# 02_ZIGBEE_CC2530.net
KiCad netlist of a schematic drawn in Altium Designer
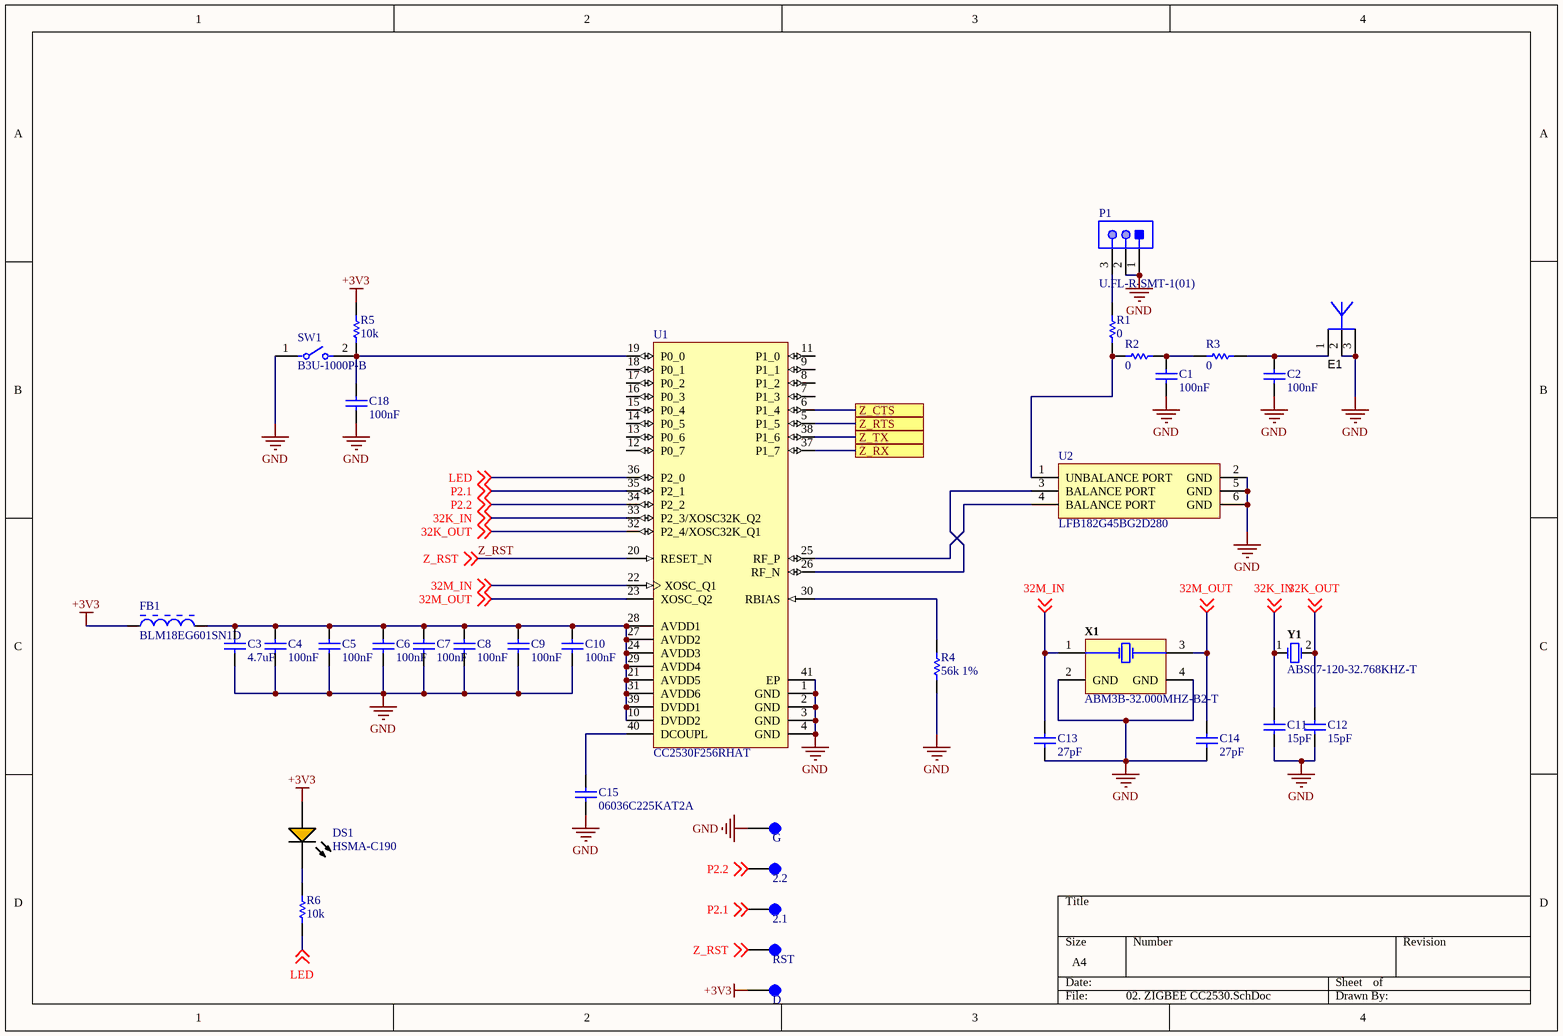
[diagram p0: 02. ZIGBEE CC2530.SchDoc]

(export (version "E")
  (design (tool "Eeschema 10.0.6"))
  (components
    (comp (ref "2.1") (value "Test Point") (footprint "TP") (libsource (lib "SyTungNguyen") (part "TP")))
    (comp (ref "2.2") (value "Test Point") (footprint "TP") (libsource (lib "SyTungNguyen") (part "TP")))
    (comp (ref "C1")
      (value "100nF")
      (footprint "CAPC1005X56X25NL10T15")
      (fields
        (field (name "MANUFACTURER") "AVX Interconnect / Elco")
        (field (name "PART NUMBER") "04026D104KAT2A")
      )
      (libsource (lib "Altium Content Vault") (part "CAP"))
    )
    (comp (ref "C2")
      (value "100nF")
      (footprint "CAPC1005X56X25NL10T15")
      (fields
        (field (name "MANUFACTURER") "AVX Interconnect / Elco")
        (field (name "PART NUMBER") "04026D104KAT2A")
      )
      (libsource (lib "Altium Content Vault") (part "CAP"))
    )
    (comp (ref "C3")
      (value "4.7uF")
      (footprint "CAPC1608X90X35NL10T15")
      (fields (field (name "PART NUMBER") "GRM188R6YA475KE15D") (field (name "MANUFACTURER") "Murata"))
      (libsource (lib "Altium Content Vault") (part "CAP"))
    )
    (comp (ref "C4")
      (value "100nF")
      (footprint "CAPC1005X56X25NL10T15")
      (fields
        (field (name "MANUFACTURER") "AVX Interconnect / Elco")
        (field (name "PART NUMBER") "04026D104KAT2A")
      )
      (libsource (lib "Altium Content Vault") (part "CAP"))
    )
    (comp (ref "C5")
      (value "100nF")
      (footprint "CAPC1005X56X25NL10T15")
      (fields
        (field (name "MANUFACTURER") "AVX Interconnect / Elco")
        (field (name "PART NUMBER") "04026D104KAT2A")
      )
      (libsource (lib "Altium Content Vault") (part "CAP"))
    )
    (comp (ref "C6")
      (value "100nF")
      (footprint "CAPC1005X56X25NL10T15")
      (fields
        (field (name "MANUFACTURER") "AVX Interconnect / Elco")
        (field (name "PART NUMBER") "04026D104KAT2A")
      )
      (libsource (lib "Altium Content Vault") (part "CAP"))
    )
    (comp (ref "C7")
      (value "100nF")
      (footprint "CAPC1005X56X25NL10T15")
      (fields
        (field (name "MANUFACTURER") "AVX Interconnect / Elco")
        (field (name "PART NUMBER") "04026D104KAT2A")
      )
      (libsource (lib "Altium Content Vault") (part "CAP"))
    )
    (comp (ref "C8")
      (value "100nF")
      (footprint "CAPC1005X56X25NL10T15")
      (fields
        (field (name "MANUFACTURER") "AVX Interconnect / Elco")
        (field (name "PART NUMBER") "04026D104KAT2A")
      )
      (libsource (lib "Altium Content Vault") (part "CAP"))
    )
    (comp (ref "C9")
      (value "100nF")
      (footprint "CAPC1005X56X25NL10T15")
      (fields
        (field (name "MANUFACTURER") "AVX Interconnect / Elco")
        (field (name "PART NUMBER") "04026D104KAT2A")
      )
      (libsource (lib "Altium Content Vault") (part "CAP"))
    )
    (comp (ref "C10")
      (value "100nF")
      (footprint "CAPC1005X56X25NL10T15")
      (fields
        (field (name "MANUFACTURER") "AVX Interconnect / Elco")
        (field (name "PART NUMBER") "04026D104KAT2A")
      )
      (libsource (lib "Altium Content Vault") (part "CAP"))
    )
    (comp (ref "C11")
      (value "15pF")
      (footprint "CAPC1005X56X25NL10T15")
      (fields
        (field (name "PART NUMBER") "04025A270FAT2A")
        (field (name "MANUFACTURER") "AVX Interconnect / Elco")
      )
      (libsource (lib "Altium Content Vault") (part "CAP"))
    )
    (comp (ref "C12")
      (value "15pF")
      (footprint "CAPC1005X56X25NL10T15")
      (fields
        (field (name "PART NUMBER") "04025A270FAT2A")
        (field (name "MANUFACTURER") "AVX Interconnect / Elco")
      )
      (libsource (lib "Altium Content Vault") (part "CAP"))
    )
    (comp (ref "C13")
      (value "27pF")
      (footprint "CAPC1005X56X25NL10T15")
      (fields
        (field (name "PART NUMBER") "04025A270FAT2A")
        (field (name "MANUFACTURER") "AVX Interconnect / Elco")
      )
      (libsource (lib "Altium Content Vault") (part "CAP"))
    )
    (comp (ref "C14")
      (value "27pF")
      (footprint "CAPC1005X56X25NL10T15")
      (fields
        (field (name "PART NUMBER") "04025A270FAT2A")
        (field (name "MANUFACTURER") "AVX Interconnect / Elco")
      )
      (libsource (lib "Altium Content Vault") (part "CAP"))
    )
    (comp (ref "C15")
      (value "06036C225KAT2A")
      (footprint "CAPC1608X90X35NL15T15")
      (fields (field (name "MANUFACTURER") "AVX Interconnect / Elco"))
      (libsource (lib "Altium Content Vault") (part "CAP"))
    )
    (comp (ref "C18")
      (value "100nF")
      (footprint "CAPC1005X56X25NL10T15")
      (fields
        (field (name "MANUFACTURER") "AVX Interconnect / Elco")
        (field (name "PART NUMBER") "04026D104KAT2A")
      )
      (libsource (lib "Altium Content Vault") (part "CAP"))
    )
    (comp (ref "D") (value "Test Point") (footprint "TP") (libsource (lib "SyTungNguyen") (part "TP")))
    (comp (ref "DS1")
      (value "HSMA-C190")
      (footprint "AVAG-HSMX-C190_V")
      (description "LED Uni-Color Amber, 60 mW, 20 mA, -40 to 85 degC, 2-Pin SMD, RoHS, Tape and Reel")
      (fields (field (name "TOLERANCE") "20ppm"))
      (libsource (lib "Altium Content Vault") (part "LED-AMBER-AK-2"))
    )
    (comp (ref "E1")
      (value "ANTENNA_DN007A")
      (footprint "2.4Ghz TI ANTENNA_DN007A")
      (description "2.4GHz PCB Antenna.  There is nothing to buy or mount.")
      (fields (field (name "SYMBOLCREATOR") "a0412235") (field (name "PUBLISHER") "Texas Instruments"))
      (libsource (lib "SyTungNguyen") (part "ANTENNA_DN007A"))
    )
    (comp (ref "FB1")
      (value "BLM18EG601SN1D")
      (footprint "MURA-BLM18-F-H1-CHIP-2_V")
      (fields (field (name "MANUFACTURER") "Murata"))
      (libsource (lib "Altium Content Vault") (part "MURA-FB-2"))
    )
    (comp (ref "G") (value "Test Point") (footprint "TP") (libsource (lib "SyTungNguyen") (part "TP")))
    (comp (ref "P1")
      (value "U.FL-R-SMT-1(01)")
      (footprint "HRS-U.FL-R-SMT-3_V")
      (description "Ultra Small Coaxial Connector, 6 GHz, -40 to 90 degC, 3-Pin SMD, RoHS, Bulk")
      (fields (field (name "MANUFACTURER") "Hirose Electric"))
      (libsource (lib "Altium Content Vault") (part "CN-1P-M-R3"))
    )
    (comp (ref "R1")
      (value "0")
      (footprint "RESC1005X40X25NL05T05")
      (description "Chip Resistor, 10 KOhm, +/- 1%, 0.1 W, -55 to 155 degC, 0402 (1005 Metric), RoHS, Tape and Reel")
      (fields (field (name "TOLERANCE") "1%") (field (name "MANUFACTURER") "Panasonic"))
      (libsource (lib "Altium Content Vault") (part "RES-2"))
    )
    (comp (ref "R2")
      (value "0")
      (footprint "RESC1005X40X25NL05T05")
      (description "Chip Resistor, 10 KOhm, +/- 1%, 0.1 W, -55 to 155 degC, 0402 (1005 Metric), RoHS, Tape and Reel")
      (fields (field (name "TOLERANCE") "1%") (field (name "MANUFACTURER") "Panasonic"))
      (libsource (lib "Altium Content Vault") (part "RES-2"))
    )
    (comp (ref "R3")
      (value "0")
      (footprint "RESC1005X40X25NL05T05")
      (description "Chip Resistor, 10 KOhm, +/- 1%, 0.1 W, -55 to 155 degC, 0402 (1005 Metric), RoHS, Tape and Reel")
      (fields (field (name "TOLERANCE") "1%") (field (name "MANUFACTURER") "Panasonic"))
      (libsource (lib "Altium Content Vault") (part "RES-2"))
    )
    (comp (ref "R4")
      (value "56k 1%")
      (footprint "RESC1609X50X30NL10T20")
      (fields (field (name "PART NUMBER") "CRCW060356K0FKEA") (field (name "MANUFACTURER") "Vishay Dale"))
      (libsource (lib "Altium Content Vault") (part "RES"))
    )
    (comp (ref "R5")
      (value "10k")
      (footprint "RESC1005X40X25NL05T05")
      (description "Chip Resistor, 10 KOhm, +/- 1%, 0.1 W, -55 to 155 degC, 0402 (1005 Metric), RoHS, Tape and Reel")
      (fields (field (name "TOLERANCE") "1%") (field (name "MANUFACTURER") "Panasonic"))
      (libsource (lib "Altium Content Vault") (part "RES-2"))
    )
    (comp (ref "R6")
      (value "10k")
      (footprint "RESC1005X40X25NL05T05")
      (description "Chip Resistor, 10 KOhm, +/- 1%, 0.1 W, -55 to 155 degC, 0402 (1005 Metric), RoHS, Tape and Reel")
      (fields (field (name "TOLERANCE") "1%") (field (name "MANUFACTURER") "Panasonic"))
      (libsource (lib "Altium Content Vault") (part "RES-2"))
    )
    (comp (ref "RST") (value "Test Point") (footprint "TP") (libsource (lib "SyTungNguyen") (part "TP")))
    (comp (ref "SW1")
      (value "B3U-1000P-B")
      (footprint "FP-B3U-1000P-B-MFG")
      (description "SWITCH TACTILE SPST-NO 0.05A 12V")
      (fields
        (field (name "OCTOPART") "https://octopart.com/b3u-1000p-b-omron-1057356")
        (field (name "MANUFACTURER") "Omron")
      )
      (libsource (lib "Altium Content Vault") (part "bb27bde45df87f1f469753f287ef5ae"))
    )
    (comp (ref "U1")
      (value "CC2530F256RHAT")
      (footprint "RHA0040H_V")
      (description "CC2530 System-on-Chip Solution for 2.4-GHz IEEE 802.15.4 and ZigBee Applications")
      (fields (field (name "MANUFACTURER") "Texas Instruments"))
      (libsource (lib "Altium Content Vault") (part "TI-CC2530RHA40-4500X4500TP"))
    )
    (comp (ref "U2")
      (value "LFB182G45BG2D280")
      (footprint "MURA-LFB182G45BG5D920-6_V")
      (description "Balance Matching Band Pass Filter, -40 to 85 degC, 6-Pin SMD, RoHS, Tape and Reel")
      (fields (field (name "MANUFACTURER") "Murata"))
      (libsource (lib "Altium Content Vault") (part "MURA-LFB182G45BG2D280-6"))
    )
    (comp (ref "X1")
      (value "ABM3B-32.000MHZ-B2-T")
      (footprint "ABRA-ABM3B_V")
      (description "Ceramic SMD Crystal, 8 MHz, +/- 20 ppm, 200 Ohm, -20 to 70 degC, 4-Pin SMD, RoHS, Tape and Reel")
      (libsource (lib "Altium Content Vault") (part "XTAL-1-3-4"))
    )
    (comp (ref "Y1")
      (value "ABS07-120-32.768KHZ-T")
      (footprint "ABRA-ABS07_A_V")
      (description "Tuning Fork Crystal, 32.768 KHz, +/- 20 ppm, -40 to 85 degC, 2-Pin SMD, RoHS, Tape and Reel")
      (fields (field (name "MANUFACTURER") "Abracon") (field (name "TOLERANCE") "20ppm"))
      (libsource (lib "Altium Content Vault") (part "XTAL-1-2-2"))
    )
  )
  (nets
    (net (code "1") (name "+3V3") (class "Default")
      (node (ref "D") (pin "1") (pintype "passive"))
      (node (ref "DS1") (pin "1") (pinfunction "A_1") (pintype "passive"))
      (node (ref "FB1") (pin "1") (pinfunction "1_1") (pintype "passive"))
      (node (ref "R5") (pin "2") (pinfunction "2_2") (pintype "passive"))
    )
    (net (code "2") (name "/Z_CTS") (class "Default")
      (node (ref "U1") (pin "6") (pinfunction "P1_4_6") (pintype "bidirectional"))
    )
    (net (code "3") (name "/Z_RTS") (class "Default")
      (node (ref "U1") (pin "5") (pinfunction "P1_5_5") (pintype "bidirectional"))
    )
    (net (code "4") (name "/Z_RX") (class "Default")
      (node (ref "U1") (pin "37") (pinfunction "P1_7_37") (pintype "bidirectional"))
    )
    (net (code "5") (name "/Z_TX") (class "Default")
      (node (ref "U1") (pin "38") (pinfunction "P1_6_38") (pintype "bidirectional"))
    )
    (net (code "6") (name "32K_IN") (class "Default")
      (node (ref "C11") (pin "1") (pinfunction "1_1") (pintype "passive"))
      (node (ref "U1") (pin "33") (pinfunction "P2_3/XOSC32K_Q2_33") (pintype "bidirectional"))
      (node (ref "Y1") (pin "1") (pinfunction "1_1") (pintype "passive"))
    )
    (net (code "7") (name "32K_OUT") (class "Default")
      (node (ref "C12") (pin "1") (pinfunction "1_1") (pintype "passive"))
      (node (ref "U1") (pin "32") (pinfunction "P2_4/XOSC32K_Q1_32") (pintype "bidirectional"))
      (node (ref "Y1") (pin "2") (pinfunction "2_2") (pintype "passive"))
    )
    (net (code "8") (name "32M_IN") (class "Default")
      (node (ref "C13") (pin "2") (pinfunction "2_2") (pintype "passive"))
      (node (ref "U1") (pin "22") (pinfunction "XOSC_Q1_22") (pintype "input"))
      (node (ref "X1") (pin "1") (pinfunction "X1_1") (pintype "passive"))
    )
    (net (code "9") (name "32M_OUT") (class "Default")
      (node (ref "C14") (pin "2") (pinfunction "2_2") (pintype "passive"))
      (node (ref "U1") (pin "23") (pinfunction "XOSC_Q2_23") (pintype "passive"))
      (node (ref "X1") (pin "3") (pinfunction "X2_3") (pintype "passive"))
    )
    (net (code "10") (name "GND") (class "Default")
      (node (ref "C1") (pin "1") (pinfunction "1_1") (pintype "passive"))
      (node (ref "C10") (pin "1") (pinfunction "1_1") (pintype "passive"))
      (node (ref "C11") (pin "2") (pinfunction "2_2") (pintype "passive"))
      (node (ref "C12") (pin "2") (pinfunction "2_2") (pintype "passive"))
      (node (ref "C13") (pin "1") (pinfunction "1_1") (pintype "passive"))
      (node (ref "C14") (pin "1") (pinfunction "1_1") (pintype "passive"))
      (node (ref "C15") (pin "1") (pinfunction "1_1") (pintype "passive"))
      (node (ref "C18") (pin "1") (pinfunction "1_1") (pintype "passive"))
      (node (ref "C2") (pin "1") (pinfunction "1_1") (pintype "passive"))
      (node (ref "C3") (pin "1") (pinfunction "1_1") (pintype "passive"))
      (node (ref "C4") (pin "1") (pinfunction "1_1") (pintype "passive"))
      (node (ref "C5") (pin "1") (pinfunction "1_1") (pintype "passive"))
      (node (ref "C6") (pin "1") (pinfunction "1_1") (pintype "passive"))
      (node (ref "C7") (pin "1") (pinfunction "1_1") (pintype "passive"))
      (node (ref "C8") (pin "1") (pinfunction "1_1") (pintype "passive"))
      (node (ref "C9") (pin "1") (pinfunction "1_1") (pintype "passive"))
      (node (ref "E1") (pin "2") (pintype "passive"))
      (node (ref "E1") (pin "3") (pintype "passive"))
      (node (ref "G") (pin "1") (pintype "passive"))
      (node (ref "P1") (pin "1") (pinfunction "1_1") (pintype "passive"))
      (node (ref "P1") (pin "2") (pinfunction "2_2") (pintype "passive"))
      (node (ref "R4") (pin "1") (pinfunction "1_1") (pintype "passive"))
      (node (ref "SW1") (pin "1") (pinfunction "1_1") (pintype "passive"))
      (node (ref "U1") (pin "1") (pinfunction "GND_1") (pintype "power_in"))
      (node (ref "U1") (pin "2") (pinfunction "GND_2") (pintype "power_in"))
      (node (ref "U1") (pin "3") (pinfunction "GND_3") (pintype "power_in"))
      (node (ref "U1") (pin "4") (pinfunction "GND_4") (pintype "power_in"))
      (node (ref "U1") (pin "41") (pinfunction "EP_41") (pintype "power_in"))
      (node (ref "U2") (pin "2") (pinfunction "GND_2") (pintype "power_in"))
      (node (ref "U2") (pin "5") (pinfunction "GND_5") (pintype "power_in"))
      (node (ref "U2") (pin "6") (pinfunction "GND_6") (pintype "power_in"))
      (node (ref "X1") (pin "2") (pinfunction "GND_2") (pintype "power_in"))
      (node (ref "X1") (pin "4") (pinfunction "GND_4") (pintype "power_in"))
    )
    (net (code "11") (name "LED") (class "Default")
      (node (ref "R6") (pin "1") (pinfunction "1_1") (pintype "passive"))
      (node (ref "U1") (pin "36") (pinfunction "P2_0_36") (pintype "bidirectional"))
    )
    (net (code "12") (name "Net-(C1-Pad2)") (class "Default")
      (node (ref "C1") (pin "2") (pinfunction "2_2") (pintype "passive"))
      (node (ref "R2") (pin "1") (pinfunction "1_1") (pintype "passive"))
      (node (ref "R3") (pin "2") (pinfunction "2_2") (pintype "passive"))
    )
    (net (code "13") (name "Net-(C2-Pad2)") (class "Default")
      (node (ref "C2") (pin "2") (pinfunction "2_2") (pintype "passive"))
      (node (ref "E1") (pin "1") (pintype "passive"))
      (node (ref "R3") (pin "1") (pinfunction "1_1") (pintype "passive"))
    )
    (net (code "14") (name "Net-(DS1-K)") (class "Default")
      (node (ref "DS1") (pin "2") (pinfunction "K_2") (pintype "passive"))
      (node (ref "R6") (pin "2") (pinfunction "2_2") (pintype "passive"))
    )
    (net (code "15") (name "Net-(P1-Pad3)") (class "Default")
      (node (ref "P1") (pin "3") (pinfunction "3_3") (pintype "passive"))
      (node (ref "R1") (pin "1") (pinfunction "1_1") (pintype "passive"))
    )
    (net (code "16") (name "Net-(U1-AVDD1)") (class "Default")
      (node (ref "C10") (pin "2") (pinfunction "2_2") (pintype "passive"))
      (node (ref "C3") (pin "2") (pinfunction "2_2") (pintype "passive"))
      (node (ref "C4") (pin "2") (pinfunction "2_2") (pintype "passive"))
      (node (ref "C5") (pin "2") (pinfunction "2_2") (pintype "passive"))
      (node (ref "C6") (pin "2") (pinfunction "2_2") (pintype "passive"))
      (node (ref "C7") (pin "2") (pinfunction "2_2") (pintype "passive"))
      (node (ref "C8") (pin "2") (pinfunction "2_2") (pintype "passive"))
      (node (ref "C9") (pin "2") (pinfunction "2_2") (pintype "passive"))
      (node (ref "FB1") (pin "2") (pinfunction "2_2") (pintype "passive"))
      (node (ref "U1") (pin "10") (pinfunction "DVDD2_10") (pintype "power_in"))
      (node (ref "U1") (pin "21") (pinfunction "AVDD5_21") (pintype "power_in"))
      (node (ref "U1") (pin "24") (pinfunction "AVDD3_24") (pintype "power_in"))
      (node (ref "U1") (pin "27") (pinfunction "AVDD2_27") (pintype "power_in"))
      (node (ref "U1") (pin "28") (pinfunction "AVDD1_28") (pintype "power_in"))
      (node (ref "U1") (pin "29") (pinfunction "AVDD4_29") (pintype "power_in"))
      (node (ref "U1") (pin "31") (pinfunction "AVDD6_31") (pintype "power_in"))
      (node (ref "U1") (pin "39") (pinfunction "DVDD1_39") (pintype "power_in"))
    )
    (net (code "17") (name "Net-(U1-DCOUPL)") (class "Default")
      (node (ref "C15") (pin "2") (pinfunction "2_2") (pintype "passive"))
      (node (ref "U1") (pin "40") (pinfunction "DCOUPL_40") (pintype "power_in"))
    )
    (net (code "18") (name "Net-(U1-P0_0)") (class "Default")
      (node (ref "C18") (pin "2") (pinfunction "2_2") (pintype "passive"))
      (node (ref "R5") (pin "1") (pinfunction "1_1") (pintype "passive"))
      (node (ref "SW1") (pin "2") (pinfunction "2_2") (pintype "passive"))
      (node (ref "U1") (pin "19") (pinfunction "P0_0_19") (pintype "bidirectional"))
    )
    (net (code "19") (name "Net-(U1-RBIAS)") (class "Default")
      (node (ref "R4") (pin "2") (pinfunction "2_2") (pintype "passive"))
      (node (ref "U1") (pin "30") (pinfunction "RBIAS_30") (pintype "input"))
    )
    (net (code "20") (name "Net-(U1-RF_N)") (class "Default")
      (node (ref "U1") (pin "26") (pinfunction "RF_N_26") (pintype "bidirectional"))
      (node (ref "U2") (pin "3") (pinfunction "BALANCE_PORT_3") (pintype "passive"))
    )
    (net (code "21") (name "Net-(U1-RF_P)") (class "Default")
      (node (ref "U1") (pin "25") (pinfunction "RF_P_25") (pintype "bidirectional"))
      (node (ref "U2") (pin "4") (pinfunction "BALANCE_PORT_4") (pintype "passive"))
    )
    (net (code "22") (name "Net-(U2-UNBALANCE_PORT)") (class "Default")
      (node (ref "R1") (pin "2") (pinfunction "2_2") (pintype "passive"))
      (node (ref "R2") (pin "2") (pinfunction "2_2") (pintype "passive"))
      (node (ref "U2") (pin "1") (pinfunction "UNBALANCE_PORT_1") (pintype "passive"))
    )
    (net (code "23") (name "P2.1") (class "Default")
      (node (ref "2.1") (pin "1") (pintype "passive"))
      (node (ref "U1") (pin "35") (pinfunction "P2_1_35") (pintype "bidirectional"))
    )
    (net (code "24") (name "P2.2") (class "Default")
      (node (ref "2.2") (pin "1") (pintype "passive"))
      (node (ref "U1") (pin "34") (pinfunction "P2_2_34") (pintype "bidirectional"))
    )
    (net (code "25") (name "Z_RST") (class "Default")
      (node (ref "RST") (pin "1") (pintype "passive"))
      (node (ref "U1") (pin "20") (pinfunction "RESET_N_20") (pintype "input"))
    )
    (net (code "26") (name "unconnected-(U1-P0_1-Pad18)") (class "Default")
      (node (ref "U1") (pin "18") (pinfunction "P0_1_18") (pintype "bidirectional"))
    )
    (net (code "27") (name "unconnected-(U1-P0_2-Pad17)") (class "Default")
      (node (ref "U1") (pin "17") (pinfunction "P0_2_17") (pintype "bidirectional"))
    )
    (net (code "28") (name "unconnected-(U1-P0_3-Pad16)") (class "Default")
      (node (ref "U1") (pin "16") (pinfunction "P0_3_16") (pintype "bidirectional"))
    )
    (net (code "29") (name "unconnected-(U1-P0_4-Pad15)") (class "Default")
      (node (ref "U1") (pin "15") (pinfunction "P0_4_15") (pintype "bidirectional"))
    )
    (net (code "30") (name "unconnected-(U1-P0_5-Pad14)") (class "Default")
      (node (ref "U1") (pin "14") (pinfunction "P0_5_14") (pintype "bidirectional"))
    )
    (net (code "31") (name "unconnected-(U1-P0_6-Pad13)") (class "Default")
      (node (ref "U1") (pin "13") (pinfunction "P0_6_13") (pintype "bidirectional"))
    )
    (net (code "32") (name "unconnected-(U1-P0_7-Pad12)") (class "Default")
      (node (ref "U1") (pin "12") (pinfunction "P0_7_12") (pintype "bidirectional"))
    )
    (net (code "33") (name "unconnected-(U1-P1_0-Pad11)") (class "Default")
      (node (ref "U1") (pin "11") (pinfunction "P1_0_11") (pintype "bidirectional"))
    )
    (net (code "34") (name "unconnected-(U1-P1_1-Pad9)") (class "Default")
      (node (ref "U1") (pin "9") (pinfunction "P1_1_9") (pintype "bidirectional"))
    )
    (net (code "35") (name "unconnected-(U1-P1_2-Pad8)") (class "Default")
      (node (ref "U1") (pin "8") (pinfunction "P1_2_8") (pintype "bidirectional"))
    )
    (net (code "36") (name "unconnected-(U1-P1_3-Pad7)") (class "Default")
      (node (ref "U1") (pin "7") (pinfunction "P1_3_7") (pintype "bidirectional"))
    )
  )
)
